# Processor.net
KiCad netlist of a schematic drawn in Altium Designer
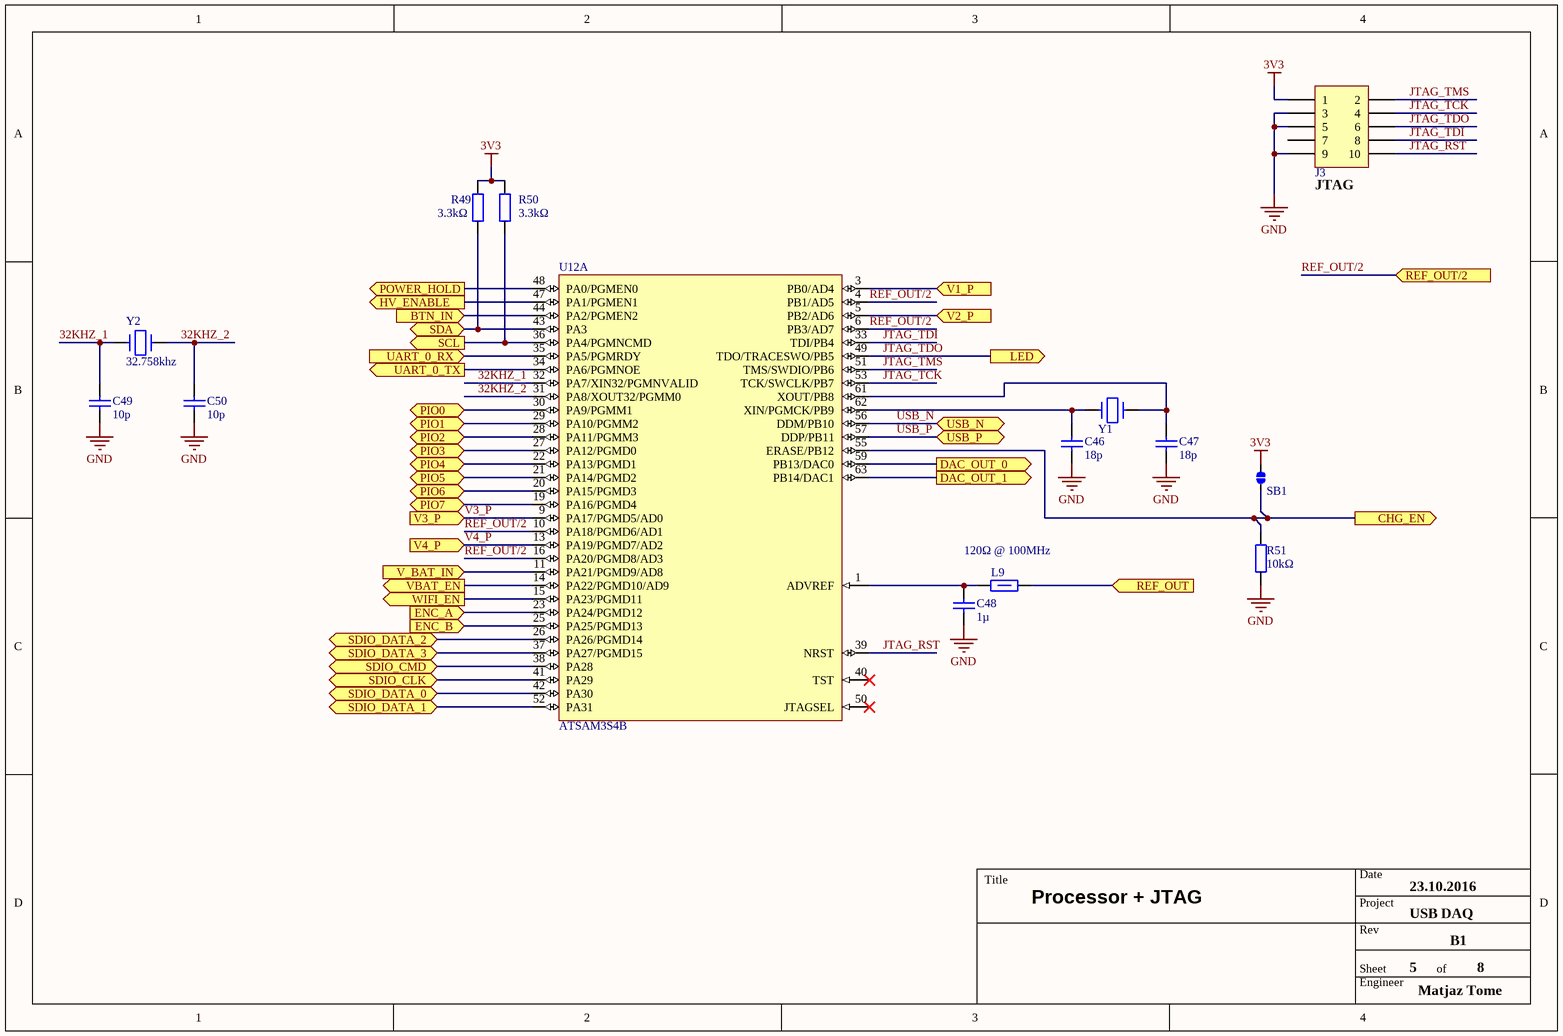
[diagram p0: Processor.SchDoc]

(export (version "E")
  (design (tool "Eeschema 10.0.6"))
  (components
    (comp (ref "C46")
      (value "18p")
      (footprint "0603C")
      (description "ceramic C0G SMD capacitor smd 0603 18pF 100V")
      (fields (field (name "PART NUMBER") "GSC0017") (field (name "MANUFACTURER") "Kemet"))
      (libsource (lib "components") (part "Capacitor"))
    )
    (comp (ref "C47")
      (value "18p")
      (footprint "0603C")
      (description "ceramic C0G SMD capacitor smd 0603 18pF 100V")
      (fields (field (name "PART NUMBER") "GSC0017") (field (name "MANUFACTURER") "Kemet"))
      (libsource (lib "components") (part "Capacitor"))
    )
    (comp (ref "C48")
      (value "1µ")
      (footprint "0603C")
      (description "ceramic X5R SMD capacitor smd 0603 1µF 50V")
      (fields (field (name "PART NUMBER") "ZSC0003") (field (name "MANUFACTURER") "Murata"))
      (libsource (lib "components") (part "Capacitor"))
    )
    (comp (ref "C49")
      (value "10p")
      (footprint "0603C")
      (description "ceramic C0G SMD capacitor smd 0603 10pF 100V")
      (fields (field (name "PART NUMBER") "GSC0019") (field (name "MANUFACTURER") "Kemet"))
      (libsource (lib "components") (part "Capacitor"))
    )
    (comp (ref "C50")
      (value "10p")
      (footprint "0603C")
      (description "ceramic C0G SMD capacitor smd 0603 10pF 100V")
      (fields (field (name "PART NUMBER") "GSC0019") (field (name "MANUFACTURER") "Kemet"))
      (libsource (lib "components") (part "Capacitor"))
    )
    (comp (ref "J3")
      (value "~")
      (footprint "HEADER_2X05_1.27mm")
      (description "Header strait 1.27mm 5way X 2")
      (fields (field (name "PART NUMBER") "XCH0006") (field (name "MANUFACTURER") "Harwin"))
      (libsource (lib "components") (part "Header 2X5"))
    )
    (comp (ref "L9")
      (value "120Ω @ 100MHz")
      (footprint "0805R")
      (description "Ferrite bead, 0.15Ω, 200mA, 0805, 120E @ 100MHz")
      (fields (field (name "PART NUMBER") "XFB0000") (field (name "MANUFACTURER") "Murata"))
      (libsource (lib "components") (part "Ferrite Bead"))
    )
    (comp (ref "R49")
      (value "3.3kΩ")
      (footprint "0603R")
      (description "resistor smd 0603 3.3kΩ 5% 0.1w")
      (fields (field (name "PART NUMBER") "XRS0055") (field (name "MANUFACTURER") "Yageo"))
      (libsource (lib "components") (part "Resistor"))
    )
    (comp (ref "R50")
      (value "3.3kΩ")
      (footprint "0603R")
      (description "resistor smd 0603 3.3kΩ 5% 0.1w")
      (fields (field (name "PART NUMBER") "XRS0055") (field (name "MANUFACTURER") "Yageo"))
      (libsource (lib "components") (part "Resistor"))
    )
    (comp (ref "R51")
      (value "10kΩ")
      (footprint "0603R")
      (description "resistor smd 0603 10kΩ 1% 0.1w")
      (fields (field (name "PART NUMBER") "YRS0016") (field (name "MANUFACTURER") "Vishay"))
      (libsource (lib "components") (part "Resistor"))
    )
    (comp (ref "SB1")
      (value "Solder bridge")
      (footprint "SB1")
      (description "Solder bridge 1mm by 2mm")
      (fields (field (name "PART NUMBER") "XXC0005"))
      (libsource (lib "components") (part "Solder bridge"))
    )
    (comp (ref "U12")
      (value "ATSAM3S4B")
      (footprint "LQFP64")
      (description "Cortex M3 ARM microcontroller")
      (fields (field (name "PART NUMBER") "XAM0003") (field (name "MANUFACTURER") "Atmel"))
      (libsource (lib "components") (part "ATSAM3SXB"))
    )
    (comp (ref "Y1")
      (value "16MHz")
      (footprint "5X3.2")
      (description "Crystal 16Mhz")
      (fields (field (name "PART NUMBER") "XCR0007") (field (name "MANUFACTURER") "TCX"))
      (libsource (lib "components") (part "CRYSTAL"))
    )
    (comp (ref "Y2")
      (value "32.758khz")
      (footprint "2X6_FLAT")
      (description "Crystal 32.768khz")
      (fields (field (name "PART NUMBER") "XCR0010") (field (name "MANUFACTURER") "RALTRON"))
      (libsource (lib "components") (part "CRYSTAL"))
    )
  )
  (nets
    (net (code "1") (name "/32KHZ_1") (class "Default")
      (node (ref "C49") (pin "2") (pinfunction "2_2") (pintype "passive"))
      (node (ref "U12") (pin "32") (pinfunction "PA7/XIN32/PGMNVALID_32") (pintype "bidirectional"))
      (node (ref "Y2") (pin "2") (pinfunction "2_2") (pintype "passive"))
    )
    (net (code "2") (name "/32KHZ_2") (class "Default")
      (node (ref "C50") (pin "2") (pinfunction "2_2") (pintype "passive"))
      (node (ref "U12") (pin "31") (pinfunction "PA8/XOUT32/PGMM0_31") (pintype "bidirectional"))
      (node (ref "Y2") (pin "1") (pinfunction "1_1") (pintype "passive"))
    )
    (net (code "3") (name "/BTN_IN") (class "Default")
      (node (ref "U12") (pin "44") (pinfunction "PA2/PGMEN2_44") (pintype "bidirectional"))
    )
    (net (code "4") (name "/CHG_EN") (class "Default")
      (node (ref "R51") (pin "2") (pinfunction "2_2") (pintype "passive"))
      (node (ref "SB1") (pin "1") (pinfunction "1_1") (pintype "power_in"))
      (node (ref "U12") (pin "55") (pinfunction "ERASE/PB12_55") (pintype "bidirectional"))
    )
    (net (code "5") (name "/DAC_OUT_0") (class "Default")
      (node (ref "U12") (pin "59") (pinfunction "PB13/DAC0_59") (pintype "bidirectional"))
    )
    (net (code "6") (name "/DAC_OUT_1") (class "Default")
      (node (ref "U12") (pin "63") (pinfunction "PB14/DAC1_63") (pintype "bidirectional"))
    )
    (net (code "7") (name "/ENC_A") (class "Default")
      (node (ref "U12") (pin "23") (pinfunction "PA24/PGMD12_23") (pintype "bidirectional"))
    )
    (net (code "8") (name "/ENC_B") (class "Default")
      (node (ref "U12") (pin "25") (pinfunction "PA25/PGMD13_25") (pintype "bidirectional"))
    )
    (net (code "9") (name "/HV_ENABLE") (class "Default")
      (node (ref "U12") (pin "47") (pinfunction "PA1/PGMEN1_47") (pintype "bidirectional"))
    )
    (net (code "10") (name "/JTAG_RST") (class "Default")
      (node (ref "J3") (pin "10") (pinfunction "10_10") (pintype "passive"))
      (node (ref "U12") (pin "39") (pinfunction "NRST_39") (pintype "bidirectional"))
    )
    (net (code "11") (name "/JTAG_TCK") (class "Default")
      (node (ref "J3") (pin "4") (pinfunction "4_4") (pintype "passive"))
      (node (ref "U12") (pin "53") (pinfunction "TCK/SWCLK/PB7_53") (pintype "bidirectional"))
    )
    (net (code "12") (name "/JTAG_TDI") (class "Default")
      (node (ref "J3") (pin "8") (pinfunction "8_8") (pintype "passive"))
      (node (ref "U12") (pin "33") (pinfunction "TDI/PB4_33") (pintype "bidirectional"))
    )
    (net (code "13") (name "/JTAG_TDO") (class "Default")
      (node (ref "J3") (pin "6") (pinfunction "6_6") (pintype "passive"))
      (node (ref "U12") (pin "49") (pinfunction "TDO/TRACESWO/PB5_49") (pintype "bidirectional"))
    )
    (net (code "14") (name "/JTAG_TMS") (class "Default")
      (node (ref "J3") (pin "2") (pinfunction "2_2") (pintype "passive"))
      (node (ref "U12") (pin "51") (pinfunction "TMS/SWDIO/PB6_51") (pintype "bidirectional"))
    )
    (net (code "15") (name "/PIO0") (class "Default")
      (node (ref "U12") (pin "30") (pinfunction "PA9/PGMM1_30") (pintype "bidirectional"))
    )
    (net (code "16") (name "/PIO1") (class "Default")
      (node (ref "U12") (pin "29") (pinfunction "PA10/PGMM2_29") (pintype "bidirectional"))
    )
    (net (code "17") (name "/PIO2") (class "Default")
      (node (ref "U12") (pin "28") (pinfunction "PA11/PGMM3_28") (pintype "bidirectional"))
    )
    (net (code "18") (name "/PIO3") (class "Default")
      (node (ref "U12") (pin "27") (pinfunction "PA12/PGMD0_27") (pintype "bidirectional"))
    )
    (net (code "19") (name "/PIO4") (class "Default")
      (node (ref "U12") (pin "22") (pinfunction "PA13/PGMD1_22") (pintype "bidirectional"))
    )
    (net (code "20") (name "/PIO5") (class "Default")
      (node (ref "U12") (pin "21") (pinfunction "PA14/PGMD2_21") (pintype "bidirectional"))
    )
    (net (code "21") (name "/PIO6") (class "Default")
      (node (ref "U12") (pin "20") (pinfunction "PA15/PGMD3_20") (pintype "bidirectional"))
    )
    (net (code "22") (name "/PIO7") (class "Default")
      (node (ref "U12") (pin "19") (pinfunction "PA16/PGMD4_19") (pintype "bidirectional"))
    )
    (net (code "23") (name "/POWER_HOLD") (class "Default")
      (node (ref "U12") (pin "48") (pinfunction "PA0/PGMEN0_48") (pintype "bidirectional"))
    )
    (net (code "24") (name "/REF_OUT") (class "Default")
      (node (ref "L9") (pin "2") (pinfunction "2_2") (pintype "passive"))
    )
    (net (code "25") (name "/REF_OUT{slash}2") (class "Default")
      (node (ref "U12") (pin "10") (pinfunction "PA18/PGMD6/AD1_10") (pintype "bidirectional"))
      (node (ref "U12") (pin "16") (pinfunction "PA20/PGMD8/AD3_16") (pintype "bidirectional"))
      (node (ref "U12") (pin "4") (pinfunction "PB1/AD5_4") (pintype "bidirectional"))
      (node (ref "U12") (pin "6") (pinfunction "PB3/AD7_6") (pintype "bidirectional"))
    )
    (net (code "26") (name "/SCL") (class "Default")
      (node (ref "R50") (pin "1") (pinfunction "1_1") (pintype "passive"))
      (node (ref "U12") (pin "36") (pinfunction "PA4/PGMNCMD_36") (pintype "bidirectional"))
    )
    (net (code "27") (name "/SDA") (class "Default")
      (node (ref "R49") (pin "1") (pinfunction "1_1") (pintype "passive"))
      (node (ref "U12") (pin "43") (pinfunction "PA3_43") (pintype "bidirectional"))
    )
    (net (code "28") (name "/SDIO_CLK") (class "Default")
      (node (ref "U12") (pin "41") (pinfunction "PA29_41") (pintype "bidirectional"))
    )
    (net (code "29") (name "/SDIO_CMD") (class "Default")
      (node (ref "U12") (pin "38") (pinfunction "PA28_38") (pintype "bidirectional"))
    )
    (net (code "30") (name "/SDIO_DATA_0") (class "Default")
      (node (ref "U12") (pin "42") (pinfunction "PA30_42") (pintype "bidirectional"))
    )
    (net (code "31") (name "/SDIO_DATA_1") (class "Default")
      (node (ref "U12") (pin "52") (pinfunction "PA31_52") (pintype "bidirectional"))
    )
    (net (code "32") (name "/SDIO_DATA_2") (class "Default")
      (node (ref "U12") (pin "26") (pinfunction "PA26/PGMD14_26") (pintype "bidirectional"))
    )
    (net (code "33") (name "/SDIO_DATA_3") (class "Default")
      (node (ref "U12") (pin "37") (pinfunction "PA27/PGMD15_37") (pintype "bidirectional"))
    )
    (net (code "34") (name "/UART_0_RX") (class "Default")
      (node (ref "U12") (pin "35") (pinfunction "PA5/PGMRDY_35") (pintype "bidirectional"))
    )
    (net (code "35") (name "/UART_0_TX") (class "Default")
      (node (ref "U12") (pin "34") (pinfunction "PA6/PGMNOE_34") (pintype "bidirectional"))
    )
    (net (code "36") (name "/USB_N") (class "Default")
      (node (ref "U12") (pin "56") (pinfunction "DDM/PB10_56") (pintype "bidirectional"))
    )
    (net (code "37") (name "/USB_P") (class "Default")
      (node (ref "U12") (pin "57") (pinfunction "DDP/PB11_57") (pintype "bidirectional"))
    )
    (net (code "38") (name "/V1_P") (class "Default")
      (node (ref "U12") (pin "3") (pinfunction "PB0/AD4_3") (pintype "bidirectional"))
    )
    (net (code "39") (name "/V2_P") (class "Default")
      (node (ref "U12") (pin "5") (pinfunction "PB2/AD6_5") (pintype "bidirectional"))
    )
    (net (code "40") (name "/V3_P") (class "Default")
      (node (ref "U12") (pin "9") (pinfunction "PA17/PGMD5/AD0_9") (pintype "bidirectional"))
    )
    (net (code "41") (name "/V4_P") (class "Default")
      (node (ref "U12") (pin "13") (pinfunction "PA19/PGMD7/AD2_13") (pintype "bidirectional"))
    )
    (net (code "42") (name "/VBAT_EN") (class "Default")
      (node (ref "U12") (pin "14") (pinfunction "PA22/PGMD10/AD9_14") (pintype "bidirectional"))
    )
    (net (code "43") (name "/V_BAT_IN") (class "Default")
      (node (ref "U12") (pin "11") (pinfunction "PA21/PGMD9/AD8_11") (pintype "bidirectional"))
    )
    (net (code "44") (name "/WIFI_EN") (class "Default")
      (node (ref "U12") (pin "15") (pinfunction "PA23/PGMD11_15") (pintype "bidirectional"))
    )
    (net (code "45") (name "3V3") (class "Default")
      (node (ref "J3") (pin "1") (pinfunction "1_1") (pintype "passive"))
      (node (ref "R49") (pin "2") (pinfunction "2_2") (pintype "passive"))
      (node (ref "R50") (pin "2") (pinfunction "2_2") (pintype "passive"))
      (node (ref "SB1") (pin "2") (pinfunction "2_2") (pintype "power_in"))
    )
    (net (code "46") (name "GND") (class "Default")
      (node (ref "C46") (pin "1") (pinfunction "1_1") (pintype "passive"))
      (node (ref "C47") (pin "1") (pinfunction "1_1") (pintype "passive"))
      (node (ref "C48") (pin "1") (pinfunction "1_1") (pintype "passive"))
      (node (ref "C49") (pin "1") (pinfunction "1_1") (pintype "passive"))
      (node (ref "C50") (pin "1") (pinfunction "1_1") (pintype "passive"))
      (node (ref "J3") (pin "3") (pinfunction "3_3") (pintype "passive"))
      (node (ref "J3") (pin "5") (pinfunction "5_5") (pintype "passive"))
      (node (ref "J3") (pin "9") (pinfunction "9_9") (pintype "passive"))
      (node (ref "R51") (pin "1") (pinfunction "1_1") (pintype "passive"))
    )
    (net (code "47") (name "Net-(U12A-ADVREF)") (class "Default")
      (node (ref "C48") (pin "2") (pinfunction "2_2") (pintype "passive"))
      (node (ref "L9") (pin "1") (pinfunction "1_1") (pintype "passive"))
      (node (ref "U12") (pin "1") (pinfunction "ADVREF_1") (pintype "input"))
    )
    (net (code "48") (name "Net-(U12A-XIN{slash}PGMCK{slash}PB9)") (class "Default")
      (node (ref "C46") (pin "2") (pinfunction "2_2") (pintype "passive"))
      (node (ref "U12") (pin "62") (pinfunction "XIN/PGMCK/PB9_62") (pintype "bidirectional"))
      (node (ref "Y1") (pin "1") (pinfunction "1_1") (pintype "passive"))
    )
    (net (code "49") (name "Net-(U12A-XOUT{slash}PB8)") (class "Default")
      (node (ref "C47") (pin "2") (pinfunction "2_2") (pintype "passive"))
      (node (ref "U12") (pin "61") (pinfunction "XOUT/PB8_61") (pintype "bidirectional"))
      (node (ref "Y1") (pin "2") (pinfunction "2_2") (pintype "passive"))
    )
    (net (code "50") (name "unconnected-(J3-Pad7)") (class "Default")
      (node (ref "J3") (pin "7") (pinfunction "7_7") (pintype "passive"))
    )
    (net (code "51") (name "unconnected-(U12A-JTAGSEL-Pad50)") (class "Default")
      (node (ref "U12") (pin "50") (pinfunction "JTAGSEL_50") (pintype "input+no_connect"))
    )
    (net (code "52") (name "unconnected-(U12A-TST-Pad40)") (class "Default")
      (node (ref "U12") (pin "40") (pinfunction "TST_40") (pintype "input+no_connect"))
    )
  )
)
